# AD5254_Breakout_Board_V3.net
KiCad netlist of a schematic drawn in EAGLE
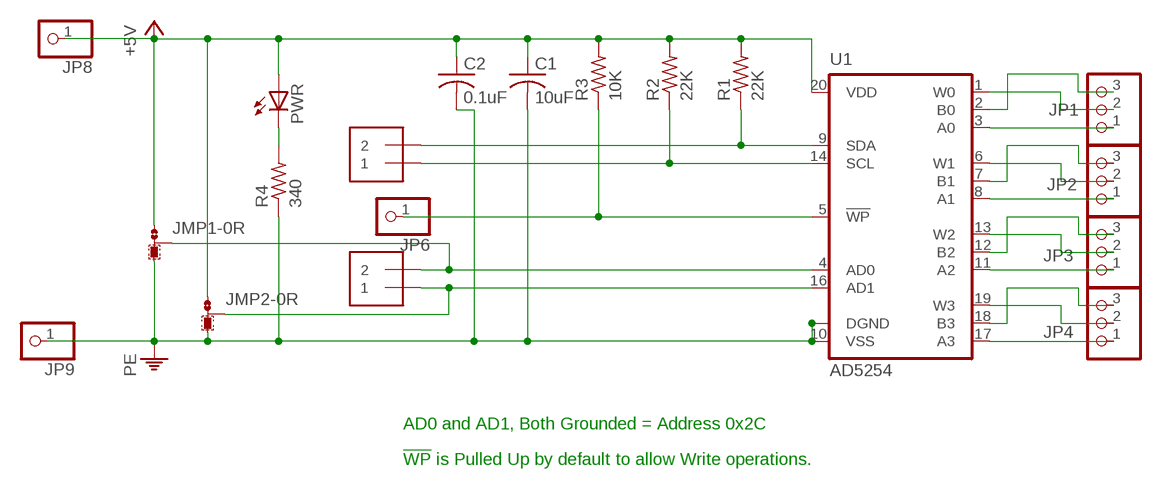
[diagram p0: schematic, sheet 1]

(export (version "E")
  (design (tool "Eeschema 10.0.6"))
  (components
    (comp (ref "C1")
      (value "10uF")
      (footprint "eagle-import:C0805")
      (libsource (lib "eagle-import") (part "C-USC0805"))
    )
    (comp (ref "C2")
      (value "0.1uF")
      (footprint "eagle-import:C0805")
      (libsource (lib "eagle-import") (part "C-USC0805"))
    )
    (comp (ref "JMP1")
      (value "0R-JUMPA")
      (footprint "eagle-import:A0R-JMP")
      (libsource (lib "eagle-import") (part "0R-JUMPA"))
    )
    (comp (ref "JMP2")
      (value "0R-JUMPA")
      (footprint "eagle-import:A0R-JMP")
      (libsource (lib "eagle-import") (part "0R-JUMPA"))
    )
    (comp (ref "JP1")
      (value "PINHD-1X3CB")
      (footprint "eagle-import:1X03-CLEANBIG")
      (libsource (lib "eagle-import") (part "PINHD-1X3CB"))
    )
    (comp (ref "JP2")
      (value "PINHD-1X3CB")
      (footprint "eagle-import:1X03-CLEANBIG")
      (libsource (lib "eagle-import") (part "PINHD-1X3CB"))
    )
    (comp (ref "JP3")
      (value "PINHD-1X3CB")
      (footprint "eagle-import:1X03-CLEANBIG")
      (libsource (lib "eagle-import") (part "PINHD-1X3CB"))
    )
    (comp (ref "JP4")
      (value "PINHD-1X3CB")
      (footprint "eagle-import:1X03-CLEANBIG")
      (libsource (lib "eagle-import") (part "PINHD-1X3CB"))
    )
    (comp (ref "JP5")
      (value "PINHD-1X2GD")
      (footprint "eagle-import:1X02-CLEANBIG")
      (libsource (lib "eagle-import") (part "PINHD-1X2GD"))
    )
    (comp (ref "JP6")
      (value "PINHD-1X1CB")
      (footprint "eagle-import:1X01-CLEANBIG")
      (libsource (lib "eagle-import") (part "PINHD-1X1CB"))
    )
    (comp (ref "JP7")
      (value "PINHD-1X2GD")
      (footprint "eagle-import:1X02-CLEANBIG")
      (libsource (lib "eagle-import") (part "PINHD-1X2GD"))
    )
    (comp (ref "JP8")
      (value "PINHD-1X1CB")
      (footprint "eagle-import:1X01-CLEANBIG")
      (libsource (lib "eagle-import") (part "PINHD-1X1CB"))
    )
    (comp (ref "JP9")
      (value "PINHD-1X1CB")
      (footprint "eagle-import:1X01-CLEANBIG")
      (libsource (lib "eagle-import") (part "PINHD-1X1CB"))
    )
    (comp (ref "PWR")
      (value "LED3MM")
      (footprint "eagle-import:LED3MM")
      (libsource (lib "eagle-import") (part "LED3MM"))
    )
    (comp (ref "R1")
      (value "22K")
      (footprint "eagle-import:M0805")
      (libsource (lib "eagle-import") (part "R-US_M0805"))
    )
    (comp (ref "R2")
      (value "22K")
      (footprint "eagle-import:M0805")
      (libsource (lib "eagle-import") (part "R-US_M0805"))
    )
    (comp (ref "R3")
      (value "10K")
      (footprint "eagle-import:M0805")
      (libsource (lib "eagle-import") (part "R-US_M0805"))
    )
    (comp (ref "R4")
      (value "340")
      (footprint "eagle-import:M0805")
      (libsource (lib "eagle-import") (part "resistor_R-US_M0805"))
    )
    (comp (ref "U1")
      (value "AD5254")
      (footprint "eagle-import:AD5254")
      (libsource (lib "eagle-import") (part "AD5254"))
    )
  )
  (nets
    (net (code "1") (name "+5V") (class "Default")
      (node (ref "C1") (pin "1") (pinfunction "1_1") (pintype "passive"))
      (node (ref "C2") (pin "1") (pinfunction "1_1") (pintype "passive"))
      (node (ref "JMP1") (pin "1") (pinfunction "1_1") (pintype "passive"))
      (node (ref "JMP2") (pin "1") (pinfunction "1_1") (pintype "passive"))
      (node (ref "JP8") (pin "1") (pinfunction "1_1") (pintype "passive"))
      (node (ref "PWR") (pin "A") (pinfunction "A_A") (pintype "passive"))
      (node (ref "R1") (pin "2") (pinfunction "2_2") (pintype "passive"))
      (node (ref "R2") (pin "2") (pinfunction "2_2") (pintype "passive"))
      (node (ref "R3") (pin "2") (pinfunction "2_2") (pintype "passive"))
      (node (ref "U1") (pin "20") (pinfunction "VDD_20") (pintype "power_in"))
    )
    (net (code "2") (name "Net-(PWR-C)") (class "Default")
      (node (ref "PWR") (pin "K") (pinfunction "C_K") (pintype "passive"))
      (node (ref "R4") (pin "2") (pinfunction "2_2") (pintype "passive"))
    )
    (net (code "3") (name "Net-(U1-A0)") (class "Default")
      (node (ref "JP1") (pin "1") (pinfunction "1_1") (pintype "passive"))
      (node (ref "U1") (pin "3") (pinfunction "A0_3") (pintype "bidirectional"))
    )
    (net (code "4") (name "Net-(U1-A1)") (class "Default")
      (node (ref "JP2") (pin "1") (pinfunction "1_1") (pintype "passive"))
      (node (ref "U1") (pin "8") (pinfunction "A1_8") (pintype "bidirectional"))
    )
    (net (code "5") (name "Net-(U1-A2)") (class "Default")
      (node (ref "JP3") (pin "1") (pinfunction "1_1") (pintype "passive"))
      (node (ref "U1") (pin "11") (pinfunction "A2_11") (pintype "bidirectional"))
    )
    (net (code "6") (name "Net-(U1-A3)") (class "Default")
      (node (ref "JP4") (pin "1") (pinfunction "1_1") (pintype "passive"))
      (node (ref "U1") (pin "17") (pinfunction "A3_17") (pintype "bidirectional"))
    )
    (net (code "7") (name "Net-(U1-AD0)") (class "Default")
      (node (ref "JMP1") (pin "2") (pinfunction "2_2") (pintype "passive"))
      (node (ref "JP7") (pin "2") (pinfunction "2_2") (pintype "passive"))
      (node (ref "U1") (pin "4") (pinfunction "AD0_4") (pintype "input"))
    )
    (net (code "8") (name "Net-(U1-AD1)") (class "Default")
      (node (ref "JMP2") (pin "2") (pinfunction "2_2") (pintype "passive"))
      (node (ref "JP7") (pin "1") (pinfunction "1_1") (pintype "passive"))
      (node (ref "U1") (pin "16") (pinfunction "AD1_16") (pintype "input"))
    )
    (net (code "9") (name "Net-(U1-B0)") (class "Default")
      (node (ref "JP1") (pin "3") (pinfunction "3_3") (pintype "passive"))
      (node (ref "U1") (pin "2") (pinfunction "B0_2") (pintype "bidirectional"))
    )
    (net (code "10") (name "Net-(U1-B1)") (class "Default")
      (node (ref "JP2") (pin "3") (pinfunction "3_3") (pintype "passive"))
      (node (ref "U1") (pin "7") (pinfunction "B1_7") (pintype "bidirectional"))
    )
    (net (code "11") (name "Net-(U1-B2)") (class "Default")
      (node (ref "JP3") (pin "3") (pinfunction "3_3") (pintype "passive"))
      (node (ref "U1") (pin "12") (pinfunction "B2_12") (pintype "bidirectional"))
    )
    (net (code "12") (name "Net-(U1-B3)") (class "Default")
      (node (ref "JP4") (pin "3") (pinfunction "3_3") (pintype "passive"))
      (node (ref "U1") (pin "18") (pinfunction "B3_18") (pintype "bidirectional"))
    )
    (net (code "13") (name "Net-(U1-SCL)") (class "Default")
      (node (ref "JP5") (pin "1") (pinfunction "1_1") (pintype "passive"))
      (node (ref "R2") (pin "1") (pinfunction "1_1") (pintype "passive"))
      (node (ref "U1") (pin "14") (pinfunction "SCL_14") (pintype "input"))
    )
    (net (code "14") (name "Net-(U1-SDA)") (class "Default")
      (node (ref "JP5") (pin "2") (pinfunction "2_2") (pintype "passive"))
      (node (ref "R1") (pin "1") (pinfunction "1_1") (pintype "passive"))
      (node (ref "U1") (pin "9") (pinfunction "SDA_9") (pintype "input"))
    )
    (net (code "15") (name "Net-(U1-W0)") (class "Default")
      (node (ref "JP1") (pin "2") (pinfunction "2_2") (pintype "passive"))
      (node (ref "U1") (pin "1") (pinfunction "W0_1") (pintype "bidirectional"))
    )
    (net (code "16") (name "Net-(U1-W1)") (class "Default")
      (node (ref "JP2") (pin "2") (pinfunction "2_2") (pintype "passive"))
      (node (ref "U1") (pin "6") (pinfunction "W1_6") (pintype "bidirectional"))
    )
    (net (code "17") (name "Net-(U1-W2)") (class "Default")
      (node (ref "JP3") (pin "2") (pinfunction "2_2") (pintype "passive"))
      (node (ref "U1") (pin "13") (pinfunction "W2_13") (pintype "bidirectional"))
    )
    (net (code "18") (name "Net-(U1-W3)") (class "Default")
      (node (ref "JP4") (pin "2") (pinfunction "2_2") (pintype "passive"))
      (node (ref "U1") (pin "19") (pinfunction "W3_19") (pintype "bidirectional"))
    )
    (net (code "19") (name "Net-(U1-~{WP})") (class "Default")
      (node (ref "JP6") (pin "1") (pinfunction "1_1") (pintype "passive"))
      (node (ref "R3") (pin "1") (pinfunction "1_1") (pintype "passive"))
      (node (ref "U1") (pin "5") (pinfunction "~{WP}_5") (pintype "input"))
    )
    (net (code "20") (name "PE") (class "Default")
      (node (ref "C1") (pin "2") (pinfunction "2_2") (pintype "passive"))
      (node (ref "C2") (pin "2") (pinfunction "2_2") (pintype "passive"))
      (node (ref "JMP1") (pin "3") (pinfunction "3_3") (pintype "passive"))
      (node (ref "JMP2") (pin "3") (pinfunction "3_3") (pintype "passive"))
      (node (ref "JP9") (pin "1") (pinfunction "1_1") (pintype "passive"))
      (node (ref "R4") (pin "1") (pinfunction "1_1") (pintype "passive"))
      (node (ref "U1") (pin "10") (pinfunction "VSS_10") (pintype "power_in"))
      (node (ref "U1") (pin "15") (pinfunction "DGND_15") (pintype "power_in"))
    )
  )
)
